# fpga.net
KiCad netlist of a schematic drawn in EAGLE
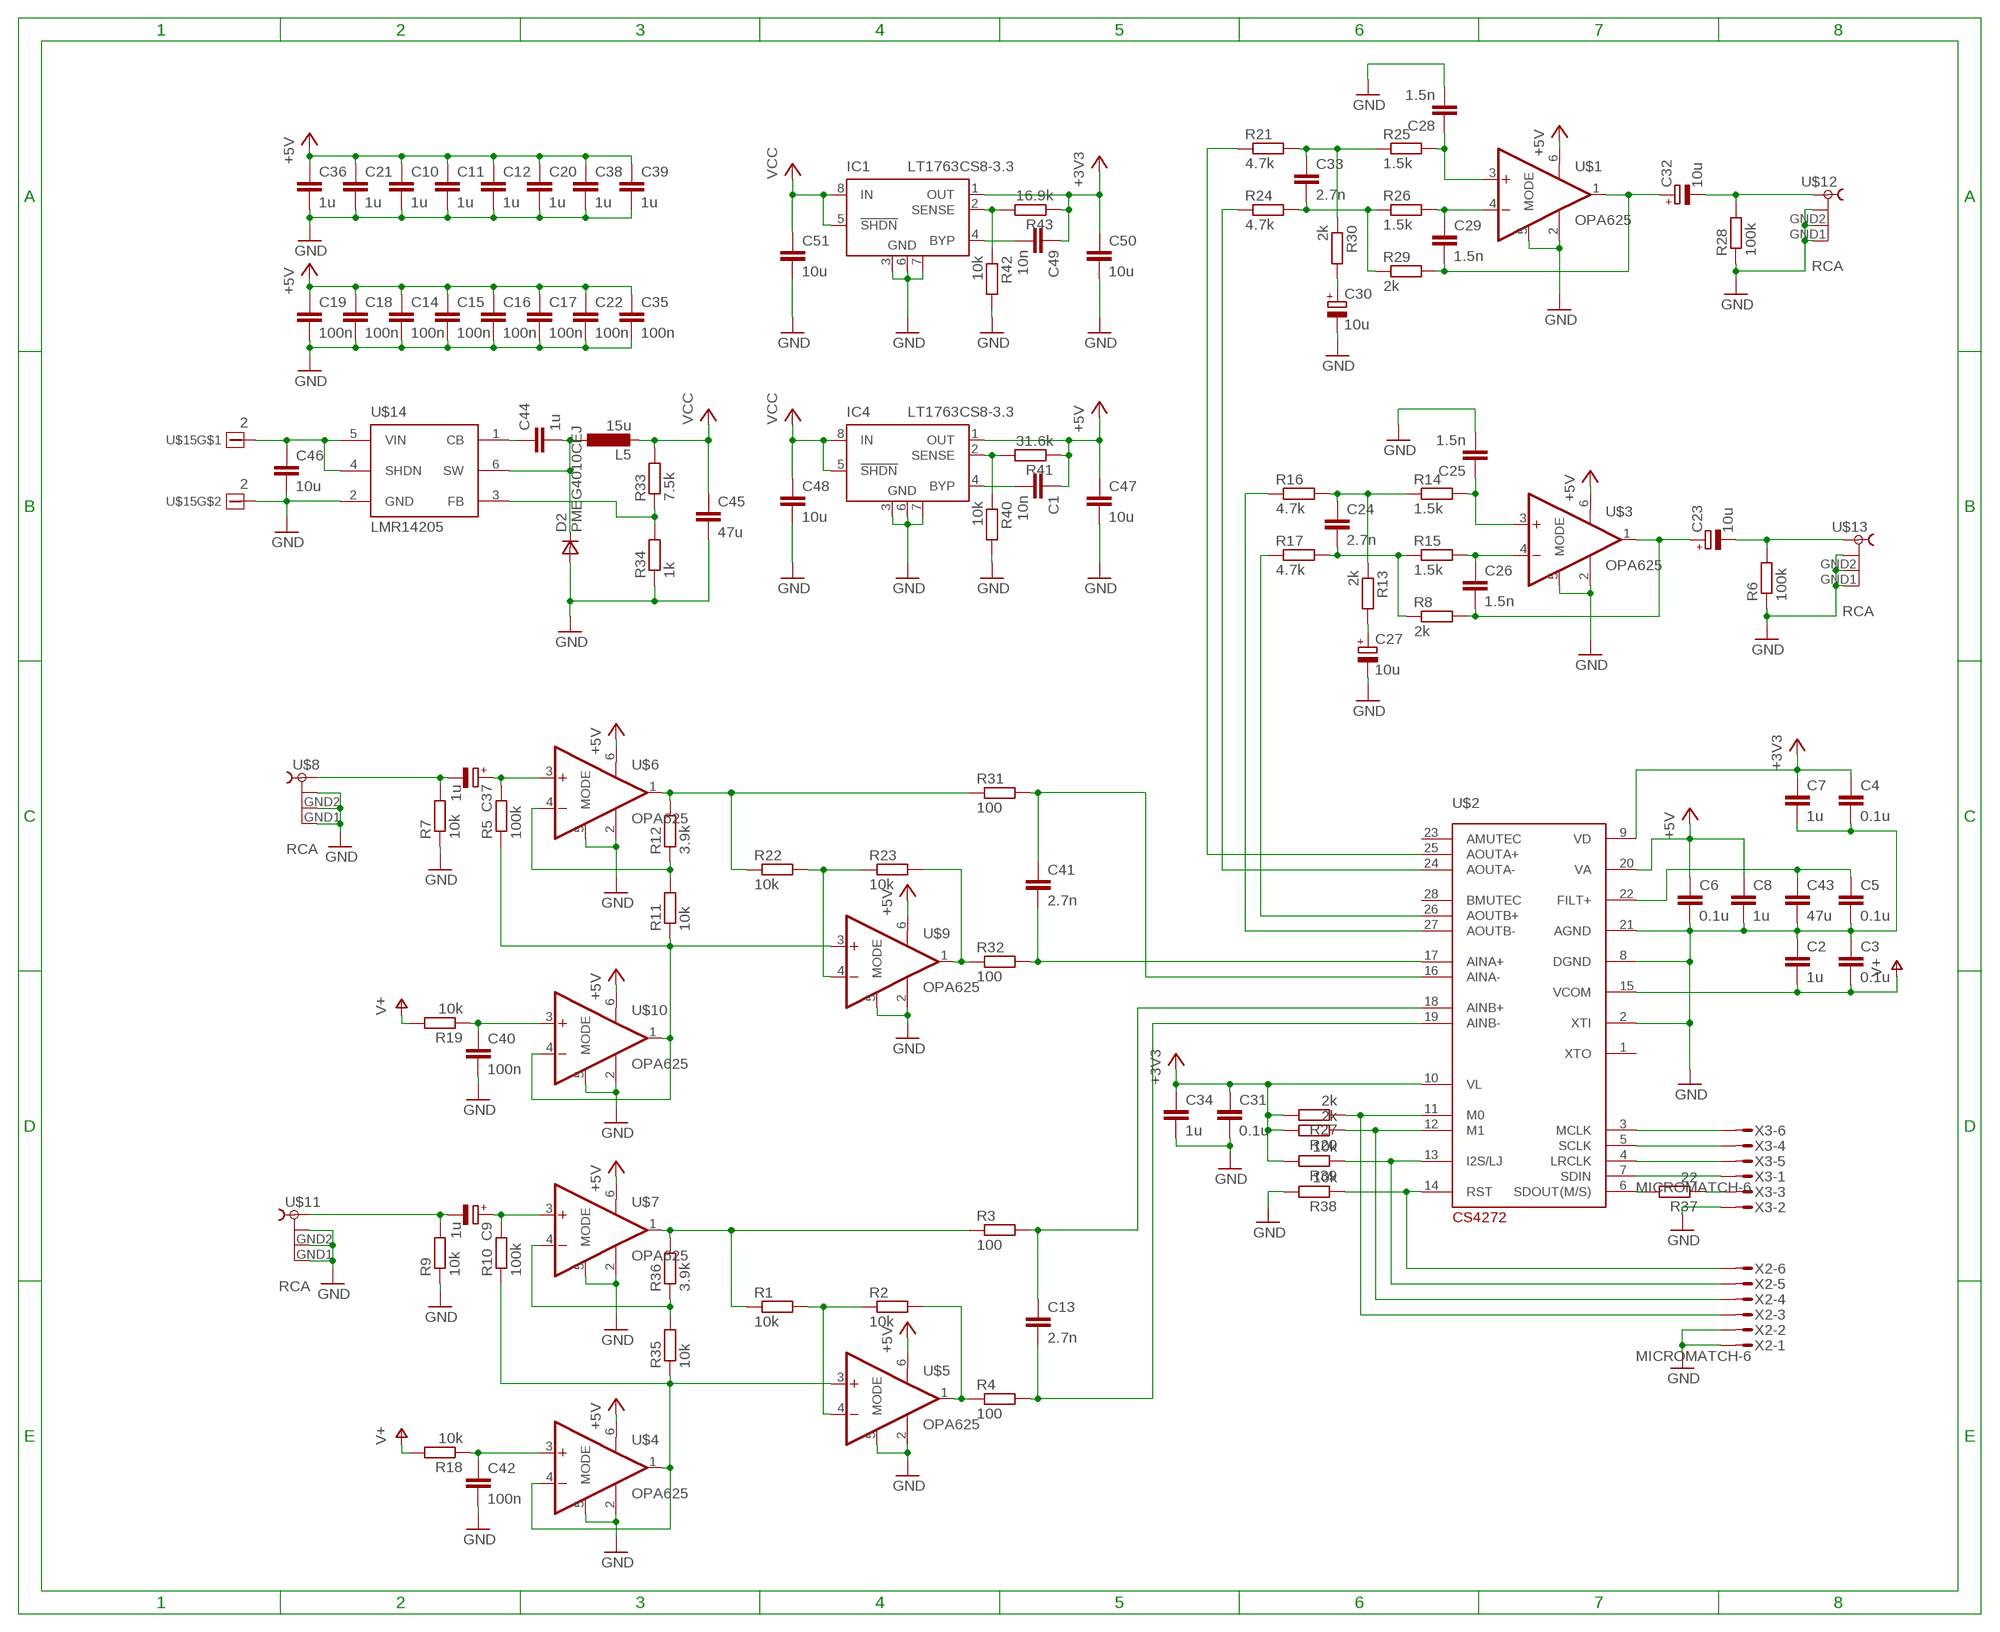
[diagram p0: schematic, sheet 1]

(export (version "E")
  (design (tool "Eeschema 10.0.6"))
  (components
    (comp (ref "C1")
      (value "10n")
      (footprint "eagle-import:C0603K")
      (libsource (lib "eagle-import") (part "C-EUC0603K"))
    )
    (comp (ref "C2")
      (value "1u")
      (footprint "eagle-import:C0603K")
      (libsource (lib "eagle-import") (part "C-EUC0603K"))
    )
    (comp (ref "C3")
      (value "0.1u")
      (footprint "eagle-import:C0603K")
      (libsource (lib "eagle-import") (part "C-EUC0603K"))
    )
    (comp (ref "C4")
      (value "0.1u")
      (footprint "eagle-import:C0603K")
      (libsource (lib "eagle-import") (part "C-EUC0603K"))
    )
    (comp (ref "C5")
      (value "0.1u")
      (footprint "eagle-import:C0603K")
      (libsource (lib "eagle-import") (part "C-EUC0603K"))
    )
    (comp (ref "C6")
      (value "0.1u")
      (footprint "eagle-import:C0603K")
      (libsource (lib "eagle-import") (part "C-EUC0603K"))
    )
    (comp (ref "C7")
      (value "1u")
      (footprint "eagle-import:C0603K")
      (libsource (lib "eagle-import") (part "C-EUC0603K"))
    )
    (comp (ref "C8")
      (value "1u")
      (footprint "eagle-import:C0603K")
      (libsource (lib "eagle-import") (part "C-EUC0603K"))
    )
    (comp (ref "C9")
      (value "1u")
      (footprint "eagle-import:153CLV-0405")
      (libsource (lib "eagle-import") (part "CPOL-EU153CLV-0405"))
    )
    (comp (ref "C10")
      (value "1u")
      (footprint "eagle-import:C0603K")
      (libsource (lib "eagle-import") (part "C-EUC0603K"))
    )
    (comp (ref "C11")
      (value "1u")
      (footprint "eagle-import:C0603K")
      (libsource (lib "eagle-import") (part "C-EUC0603K"))
    )
    (comp (ref "C12")
      (value "1u")
      (footprint "eagle-import:C0603K")
      (libsource (lib "eagle-import") (part "C-EUC0603K"))
    )
    (comp (ref "C13")
      (value "2.7n")
      (footprint "eagle-import:C0603K")
      (libsource (lib "eagle-import") (part "C-EUC0603K"))
    )
    (comp (ref "C14")
      (value "100n")
      (footprint "eagle-import:C0603K")
      (libsource (lib "eagle-import") (part "C-EUC0603K"))
    )
    (comp (ref "C15")
      (value "100n")
      (footprint "eagle-import:C0603K")
      (libsource (lib "eagle-import") (part "C-EUC0603K"))
    )
    (comp (ref "C16")
      (value "100n")
      (footprint "eagle-import:C0603K")
      (libsource (lib "eagle-import") (part "C-EUC0603K"))
    )
    (comp (ref "C17")
      (value "100n")
      (footprint "eagle-import:C0603K")
      (libsource (lib "eagle-import") (part "C-EUC0603K"))
    )
    (comp (ref "C18")
      (value "100n")
      (footprint "eagle-import:C0603K")
      (libsource (lib "eagle-import") (part "C-EUC0603K"))
    )
    (comp (ref "C19")
      (value "100n")
      (footprint "eagle-import:C0603K")
      (libsource (lib "eagle-import") (part "C-EUC0603K"))
    )
    (comp (ref "C20")
      (value "1u")
      (footprint "eagle-import:C0603K")
      (libsource (lib "eagle-import") (part "C-EUC0603K"))
    )
    (comp (ref "C21")
      (value "1u")
      (footprint "eagle-import:C0603K")
      (libsource (lib "eagle-import") (part "C-EUC0603K"))
    )
    (comp (ref "C22")
      (value "100n")
      (footprint "eagle-import:C0603K")
      (libsource (lib "eagle-import") (part "C-EUC0603K"))
    )
    (comp (ref "C23")
      (value "10u")
      (footprint "eagle-import:153CLV-0405")
      (libsource (lib "eagle-import") (part "CPOL-EU153CLV-0405"))
    )
    (comp (ref "C24")
      (value "2.7n")
      (footprint "eagle-import:C0603K")
      (libsource (lib "eagle-import") (part "C-EUC0603K"))
    )
    (comp (ref "C25")
      (value "1.5n")
      (footprint "eagle-import:C0603K")
      (libsource (lib "eagle-import") (part "C-EUC0603K"))
    )
    (comp (ref "C26")
      (value "1.5n")
      (footprint "eagle-import:C0603K")
      (libsource (lib "eagle-import") (part "C-EUC0603K"))
    )
    (comp (ref "C27")
      (value "10u")
      (footprint "eagle-import:153CLV-0405")
      (libsource (lib "eagle-import") (part "CPOL-EU153CLV-0405"))
    )
    (comp (ref "C28")
      (value "1.5n")
      (footprint "eagle-import:C0603K")
      (libsource (lib "eagle-import") (part "C-EUC0603K"))
    )
    (comp (ref "C29")
      (value "1.5n")
      (footprint "eagle-import:C0603K")
      (libsource (lib "eagle-import") (part "C-EUC0603K"))
    )
    (comp (ref "C30")
      (value "10u")
      (footprint "eagle-import:153CLV-0405")
      (libsource (lib "eagle-import") (part "CPOL-EU153CLV-0405"))
    )
    (comp (ref "C31")
      (value "0.1u")
      (footprint "eagle-import:C0603K")
      (libsource (lib "eagle-import") (part "C-EUC0603K"))
    )
    (comp (ref "C32")
      (value "10u")
      (footprint "eagle-import:153CLV-0405")
      (libsource (lib "eagle-import") (part "CPOL-EU153CLV-0405"))
    )
    (comp (ref "C33")
      (value "2.7n")
      (footprint "eagle-import:C0603K")
      (libsource (lib "eagle-import") (part "C-EUC0603K"))
    )
    (comp (ref "C34")
      (value "1u")
      (footprint "eagle-import:C0603K")
      (libsource (lib "eagle-import") (part "C-EUC0603K"))
    )
    (comp (ref "C35")
      (value "100n")
      (footprint "eagle-import:C0603K")
      (libsource (lib "eagle-import") (part "C-EUC0603K"))
    )
    (comp (ref "C36")
      (value "1u")
      (footprint "eagle-import:C0603K")
      (libsource (lib "eagle-import") (part "C-EUC0603K"))
    )
    (comp (ref "C37")
      (value "1u")
      (footprint "eagle-import:153CLV-0405")
      (libsource (lib "eagle-import") (part "CPOL-EU153CLV-0405"))
    )
    (comp (ref "C38")
      (value "1u")
      (footprint "eagle-import:C0603K")
      (libsource (lib "eagle-import") (part "C-EUC0603K"))
    )
    (comp (ref "C39")
      (value "1u")
      (footprint "eagle-import:C0603K")
      (libsource (lib "eagle-import") (part "C-EUC0603K"))
    )
    (comp (ref "C40")
      (value "100n")
      (footprint "eagle-import:C0603K")
      (libsource (lib "eagle-import") (part "C-EUC0603K"))
    )
    (comp (ref "C41")
      (value "2.7n")
      (footprint "eagle-import:C0603K")
      (libsource (lib "eagle-import") (part "C-EUC0603K"))
    )
    (comp (ref "C42")
      (value "100n")
      (footprint "eagle-import:C0603K")
      (libsource (lib "eagle-import") (part "C-EUC0603K"))
    )
    (comp (ref "C43")
      (value "47u")
      (footprint "eagle-import:C0805")
      (libsource (lib "eagle-import") (part "C-EUC0805"))
    )
    (comp (ref "C44")
      (value "1u")
      (footprint "eagle-import:C0603K")
      (libsource (lib "eagle-import") (part "C-EUC0603K"))
    )
    (comp (ref "C45")
      (value "47u")
      (footprint "eagle-import:C1206")
      (libsource (lib "eagle-import") (part "C-EUC1206"))
    )
    (comp (ref "C46")
      (value "10u")
      (footprint "eagle-import:C0805")
      (libsource (lib "eagle-import") (part "C-EUC0805"))
    )
    (comp (ref "C47")
      (value "10u")
      (footprint "eagle-import:C0603K")
      (libsource (lib "eagle-import") (part "C-EUC0603K"))
    )
    (comp (ref "C48")
      (value "10u")
      (footprint "eagle-import:C0603K")
      (libsource (lib "eagle-import") (part "C-EUC0603K"))
    )
    (comp (ref "C49")
      (value "10n")
      (footprint "eagle-import:C0603K")
      (libsource (lib "eagle-import") (part "C-EUC0603K"))
    )
    (comp (ref "C50")
      (value "10u")
      (footprint "eagle-import:C0603K")
      (libsource (lib "eagle-import") (part "C-EUC0603K"))
    )
    (comp (ref "C51")
      (value "10u")
      (footprint "eagle-import:C0603K")
      (libsource (lib "eagle-import") (part "C-EUC0603K"))
    )
    (comp (ref "D2")
      (value "PMEG4010CEJ")
      (footprint "eagle-import:SOD323")
      (fields (field (name "MPN") "CDSOD323-T05C"))
      (libsource (lib "eagle-import") (part "DSOD323"))
    )
    (comp (ref "IC1")
      (value "LT1763CS8-3.3")
      (footprint "eagle-import:SOIC8")
      (libsource (lib "eagle-import") (part "LT1763CS8-3.3"))
    )
    (comp (ref "IC4")
      (value "LT1763CS8-3.3")
      (footprint "eagle-import:SOIC8")
      (libsource (lib "eagle-import") (part "LT1763CS8-3.3"))
    )
    (comp (ref "L5")
      (value "15u")
      (footprint "eagle-import:AAA")
      (libsource (lib "eagle-import") (part "L-EU"))
    )
    (comp (ref "R1")
      (value "10k")
      (footprint "eagle-import:R0603")
      (libsource (lib "eagle-import") (part "R-EU_R0603"))
    )
    (comp (ref "R2")
      (value "10k")
      (footprint "eagle-import:R0603")
      (libsource (lib "eagle-import") (part "R-EU_R0603"))
    )
    (comp (ref "R3")
      (value "100")
      (footprint "eagle-import:R0603")
      (libsource (lib "eagle-import") (part "R-EU_R0603"))
    )
    (comp (ref "R4")
      (value "100")
      (footprint "eagle-import:R0603")
      (libsource (lib "eagle-import") (part "R-EU_R0603"))
    )
    (comp (ref "R5")
      (value "100k")
      (footprint "eagle-import:R0603")
      (libsource (lib "eagle-import") (part "R-EU_R0603"))
    )
    (comp (ref "R6")
      (value "100k")
      (footprint "eagle-import:R0603")
      (libsource (lib "eagle-import") (part "R-EU_R0603"))
    )
    (comp (ref "R7")
      (value "10k")
      (footprint "eagle-import:R0603")
      (libsource (lib "eagle-import") (part "R-EU_R0603"))
    )
    (comp (ref "R8")
      (value "2k")
      (footprint "eagle-import:R0603")
      (libsource (lib "eagle-import") (part "R-EU_R0603"))
    )
    (comp (ref "R9")
      (value "10k")
      (footprint "eagle-import:R0603")
      (libsource (lib "eagle-import") (part "R-EU_R0603"))
    )
    (comp (ref "R10")
      (value "100k")
      (footprint "eagle-import:R0603")
      (libsource (lib "eagle-import") (part "R-EU_R0603"))
    )
    (comp (ref "R11")
      (value "10k")
      (footprint "eagle-import:R0603")
      (libsource (lib "eagle-import") (part "R-EU_R0603"))
    )
    (comp (ref "R12")
      (value "3.9k")
      (footprint "eagle-import:R0603")
      (libsource (lib "eagle-import") (part "R-EU_R0603"))
    )
    (comp (ref "R13")
      (value "2k")
      (footprint "eagle-import:R0603")
      (libsource (lib "eagle-import") (part "R-EU_R0603"))
    )
    (comp (ref "R14")
      (value "1.5k")
      (footprint "eagle-import:R0603")
      (libsource (lib "eagle-import") (part "R-EU_R0603"))
    )
    (comp (ref "R15")
      (value "1.5k")
      (footprint "eagle-import:R0603")
      (libsource (lib "eagle-import") (part "R-EU_R0603"))
    )
    (comp (ref "R16")
      (value "4.7k")
      (footprint "eagle-import:R0603")
      (libsource (lib "eagle-import") (part "R-EU_R0603"))
    )
    (comp (ref "R17")
      (value "4.7k")
      (footprint "eagle-import:R0603")
      (libsource (lib "eagle-import") (part "R-EU_R0603"))
    )
    (comp (ref "R18")
      (value "10k")
      (footprint "eagle-import:R0603")
      (libsource (lib "eagle-import") (part "R-EU_R0603"))
    )
    (comp (ref "R19")
      (value "10k")
      (footprint "eagle-import:R0603")
      (libsource (lib "eagle-import") (part "R-EU_R0603"))
    )
    (comp (ref "R20")
      (value "2k")
      (footprint "eagle-import:R0603")
      (libsource (lib "eagle-import") (part "R-EU_R0603"))
    )
    (comp (ref "R21")
      (value "4.7k")
      (footprint "eagle-import:R0603")
      (libsource (lib "eagle-import") (part "R-EU_R0603"))
    )
    (comp (ref "R22")
      (value "10k")
      (footprint "eagle-import:R0603")
      (libsource (lib "eagle-import") (part "R-EU_R0603"))
    )
    (comp (ref "R23")
      (value "10k")
      (footprint "eagle-import:R0603")
      (libsource (lib "eagle-import") (part "R-EU_R0603"))
    )
    (comp (ref "R24")
      (value "4.7k")
      (footprint "eagle-import:R0603")
      (libsource (lib "eagle-import") (part "R-EU_R0603"))
    )
    (comp (ref "R25")
      (value "1.5k")
      (footprint "eagle-import:R0603")
      (libsource (lib "eagle-import") (part "R-EU_R0603"))
    )
    (comp (ref "R26")
      (value "1.5k")
      (footprint "eagle-import:R0603")
      (libsource (lib "eagle-import") (part "R-EU_R0603"))
    )
    (comp (ref "R27")
      (value "2k")
      (footprint "eagle-import:R0603")
      (libsource (lib "eagle-import") (part "R-EU_R0603"))
    )
    (comp (ref "R28")
      (value "100k")
      (footprint "eagle-import:R0603")
      (libsource (lib "eagle-import") (part "R-EU_R0603"))
    )
    (comp (ref "R29")
      (value "2k")
      (footprint "eagle-import:R0603")
      (libsource (lib "eagle-import") (part "R-EU_R0603"))
    )
    (comp (ref "R30")
      (value "2k")
      (footprint "eagle-import:R0603")
      (libsource (lib "eagle-import") (part "R-EU_R0603"))
    )
    (comp (ref "R31")
      (value "100")
      (footprint "eagle-import:R0603")
      (libsource (lib "eagle-import") (part "R-EU_R0603"))
    )
    (comp (ref "R32")
      (value "100")
      (footprint "eagle-import:R0603")
      (libsource (lib "eagle-import") (part "R-EU_R0603"))
    )
    (comp (ref "R33")
      (value "7.5k")
      (footprint "eagle-import:R0603")
      (libsource (lib "eagle-import") (part "R-EU_R0603"))
    )
    (comp (ref "R34")
      (value "1k")
      (footprint "eagle-import:R0603")
      (libsource (lib "eagle-import") (part "R-EU_R0603"))
    )
    (comp (ref "R35")
      (value "10k")
      (footprint "eagle-import:R0603")
      (libsource (lib "eagle-import") (part "R-EU_R0603"))
    )
    (comp (ref "R36")
      (value "3.9k")
      (footprint "eagle-import:R0603")
      (libsource (lib "eagle-import") (part "R-EU_R0603"))
    )
    (comp (ref "R37")
      (value "22")
      (footprint "eagle-import:R0603")
      (libsource (lib "eagle-import") (part "R-EU_R0603"))
    )
    (comp (ref "R38")
      (value "10k")
      (footprint "eagle-import:R0603")
      (libsource (lib "eagle-import") (part "R-EU_R0603"))
    )
    (comp (ref "R39")
      (value "10k")
      (footprint "eagle-import:R0603")
      (libsource (lib "eagle-import") (part "R-EU_R0603"))
    )
    (comp (ref "R40")
      (value "10k")
      (footprint "eagle-import:R0603")
      (libsource (lib "eagle-import") (part "R-EU_R0603"))
    )
    (comp (ref "R41")
      (value "31.6k")
      (footprint "eagle-import:R0603")
      (libsource (lib "eagle-import") (part "R-EU_R0603"))
    )
    (comp (ref "R42")
      (value "10k")
      (footprint "eagle-import:R0603")
      (libsource (lib "eagle-import") (part "R-EU_R0603"))
    )
    (comp (ref "R43")
      (value "16.9k")
      (footprint "eagle-import:R0603")
      (libsource (lib "eagle-import") (part "R-EU_R0603"))
    )
    (comp (ref "U$1")
      (value "OPA625")
      (footprint "eagle-import:SOT23-6")
      (libsource (lib "eagle-import") (part "OPA625"))
    )
    (comp (ref "U$2")
      (value "CS4272")
      (footprint "eagle-import:TSSOP28")
      (libsource (lib "eagle-import") (part "CS4272"))
    )
    (comp (ref "U$3")
      (value "OPA625")
      (footprint "eagle-import:SOT23-6")
      (libsource (lib "eagle-import") (part "OPA625"))
    )
    (comp (ref "U$4")
      (value "OPA625")
      (footprint "eagle-import:SOT23-6")
      (libsource (lib "eagle-import") (part "OPA625"))
    )
    (comp (ref "U$5")
      (value "OPA625")
      (footprint "eagle-import:SOT23-6")
      (libsource (lib "eagle-import") (part "OPA625"))
    )
    (comp (ref "U$6")
      (value "OPA625")
      (footprint "eagle-import:SOT23-6")
      (libsource (lib "eagle-import") (part "OPA625"))
    )
    (comp (ref "U$7")
      (value "OPA625")
      (footprint "eagle-import:SOT23-6")
      (libsource (lib "eagle-import") (part "OPA625"))
    )
    (comp (ref "U$8")
      (value "RCA")
      (footprint "eagle-import:RCA")
      (libsource (lib "eagle-import") (part "RCA"))
    )
    (comp (ref "U$9")
      (value "OPA625")
      (footprint "eagle-import:SOT23-6")
      (libsource (lib "eagle-import") (part "OPA625"))
    )
    (comp (ref "U$10")
      (value "OPA625")
      (footprint "eagle-import:SOT23-6")
      (libsource (lib "eagle-import") (part "OPA625"))
    )
    (comp (ref "U$11")
      (value "RCA")
      (footprint "eagle-import:RCA")
      (libsource (lib "eagle-import") (part "RCA"))
    )
    (comp (ref "U$12")
      (value "RCA")
      (footprint "eagle-import:RCA")
      (libsource (lib "eagle-import") (part "RCA"))
    )
    (comp (ref "U$13")
      (value "RCA")
      (footprint "eagle-import:RCA")
      (libsource (lib "eagle-import") (part "RCA"))
    )
    (comp (ref "U$14")
      (value "LMR14205")
      (footprint "eagle-import:TSOT23-6_DDC")
      (libsource (lib "eagle-import") (part "LMR14205"))
    )
    (comp (ref "U$15") (value "2") (footprint "eagle-import:2") (libsource (lib "eagle-import") (part "2")))
    (comp (ref "X2")
      (value "MICROMATCH-6")
      (footprint "eagle-import:MICROMATCH-6")
      (fields (field (name "MPN") "7-215464-6"))
      (libsource (lib "eagle-import") (part "MICROMATCH-6"))
    )
    (comp (ref "X3")
      (value "MICROMATCH-6")
      (footprint "eagle-import:MICROMATCH-6")
      (fields (field (name "MPN") "7-215464-6"))
      (libsource (lib "eagle-import") (part "MICROMATCH-6"))
    )
  )
  (nets
    (net (code "1") (name "+3V3") (class "Default")
      (node (ref "C31") (pin "1") (pinfunction "1_1") (pintype "passive"))
      (node (ref "C34") (pin "1") (pinfunction "1_1") (pintype "passive"))
      (node (ref "C4") (pin "1") (pinfunction "1_1") (pintype "passive"))
      (node (ref "C49") (pin "1") (pinfunction "1_1") (pintype "passive"))
      (node (ref "C50") (pin "1") (pinfunction "1_1") (pintype "passive"))
      (node (ref "C7") (pin "1") (pinfunction "1_1") (pintype "passive"))
      (node (ref "IC1") (pin "1") (pinfunction "OUT_1") (pintype "passive"))
      (node (ref "R20") (pin "2") (pinfunction "2_2") (pintype "passive"))
      (node (ref "R27") (pin "2") (pinfunction "2_2") (pintype "passive"))
      (node (ref "R39") (pin "2") (pinfunction "2_2") (pintype "passive"))
      (node (ref "R43") (pin "1") (pinfunction "1_1") (pintype "passive"))
      (node (ref "U$2") (pin "10") (pinfunction "VL_10") (pintype "bidirectional"))
      (node (ref "U$2") (pin "9") (pinfunction "VD_9") (pintype "bidirectional"))
    )
    (net (code "2") (name "+5V") (class "Default")
      (node (ref "C1") (pin "1") (pinfunction "1_1") (pintype "passive"))
      (node (ref "C10") (pin "1") (pinfunction "1_1") (pintype "passive"))
      (node (ref "C11") (pin "1") (pinfunction "1_1") (pintype "passive"))
      (node (ref "C12") (pin "1") (pinfunction "1_1") (pintype "passive"))
      (node (ref "C14") (pin "1") (pinfunction "1_1") (pintype "passive"))
      (node (ref "C15") (pin "1") (pinfunction "1_1") (pintype "passive"))
      (node (ref "C16") (pin "1") (pinfunction "1_1") (pintype "passive"))
      (node (ref "C17") (pin "1") (pinfunction "1_1") (pintype "passive"))
      (node (ref "C18") (pin "1") (pinfunction "1_1") (pintype "passive"))
      (node (ref "C19") (pin "1") (pinfunction "1_1") (pintype "passive"))
      (node (ref "C20") (pin "1") (pinfunction "1_1") (pintype "passive"))
      (node (ref "C21") (pin "1") (pinfunction "1_1") (pintype "passive"))
      (node (ref "C22") (pin "1") (pinfunction "1_1") (pintype "passive"))
      (node (ref "C35") (pin "1") (pinfunction "1_1") (pintype "passive"))
      (node (ref "C36") (pin "1") (pinfunction "1_1") (pintype "passive"))
      (node (ref "C38") (pin "1") (pinfunction "1_1") (pintype "passive"))
      (node (ref "C39") (pin "1") (pinfunction "1_1") (pintype "passive"))
      (node (ref "C47") (pin "1") (pinfunction "1_1") (pintype "passive"))
      (node (ref "C6") (pin "1") (pinfunction "1_1") (pintype "passive"))
      (node (ref "C8") (pin "1") (pinfunction "1_1") (pintype "passive"))
      (node (ref "IC4") (pin "1") (pinfunction "OUT_1") (pintype "passive"))
      (node (ref "R41") (pin "1") (pinfunction "1_1") (pintype "passive"))
      (node (ref "U$1") (pin "6") (pinfunction "V+_6") (pintype "power_in"))
      (node (ref "U$10") (pin "6") (pinfunction "V+_6") (pintype "power_in"))
      (node (ref "U$2") (pin "20") (pinfunction "VA_20") (pintype "bidirectional"))
      (node (ref "U$3") (pin "6") (pinfunction "V+_6") (pintype "power_in"))
      (node (ref "U$4") (pin "6") (pinfunction "V+_6") (pintype "power_in"))
      (node (ref "U$5") (pin "6") (pinfunction "V+_6") (pintype "power_in"))
      (node (ref "U$6") (pin "6") (pinfunction "V+_6") (pintype "power_in"))
      (node (ref "U$7") (pin "6") (pinfunction "V+_6") (pintype "power_in"))
      (node (ref "U$9") (pin "6") (pinfunction "V+_6") (pintype "power_in"))
    )
    (net (code "3") (name "GND") (class "Default")
      (node (ref "C10") (pin "2") (pinfunction "2_2") (pintype "passive"))
      (node (ref "C11") (pin "2") (pinfunction "2_2") (pintype "passive"))
      (node (ref "C12") (pin "2") (pinfunction "2_2") (pintype "passive"))
      (node (ref "C14") (pin "2") (pinfunction "2_2") (pintype "passive"))
      (node (ref "C15") (pin "2") (pinfunction "2_2") (pintype "passive"))
      (node (ref "C16") (pin "2") (pinfunction "2_2") (pintype "passive"))
      (node (ref "C17") (pin "2") (pinfunction "2_2") (pintype "passive"))
      (node (ref "C18") (pin "2") (pinfunction "2_2") (pintype "passive"))
      (node (ref "C19") (pin "2") (pinfunction "2_2") (pintype "passive"))
      (node (ref "C2") (pin "1") (pinfunction "1_1") (pintype "passive"))
      (node (ref "C20") (pin "2") (pinfunction "2_2") (pintype "passive"))
      (node (ref "C21") (pin "2") (pinfunction "2_2") (pintype "passive"))
      (node (ref "C22") (pin "2") (pinfunction "2_2") (pintype "passive"))
      (node (ref "C25") (pin "2") (pinfunction "2_2") (pintype "passive"))
      (node (ref "C27") (pin "-") (pinfunction "-_-") (pintype "passive"))
      (node (ref "C28") (pin "2") (pinfunction "2_2") (pintype "passive"))
      (node (ref "C3") (pin "1") (pinfunction "1_1") (pintype "passive"))
      (node (ref "C30") (pin "-") (pinfunction "-_-") (pintype "passive"))
      (node (ref "C31") (pin "2") (pinfunction "2_2") (pintype "passive"))
      (node (ref "C34") (pin "2") (pinfunction "2_2") (pintype "passive"))
      (node (ref "C35") (pin "2") (pinfunction "2_2") (pintype "passive"))
      (node (ref "C36") (pin "2") (pinfunction "2_2") (pintype "passive"))
      (node (ref "C38") (pin "2") (pinfunction "2_2") (pintype "passive"))
      (node (ref "C39") (pin "2") (pinfunction "2_2") (pintype "passive"))
      (node (ref "C4") (pin "2") (pinfunction "2_2") (pintype "passive"))
      (node (ref "C40") (pin "2") (pinfunction "2_2") (pintype "passive"))
      (node (ref "C42") (pin "2") (pinfunction "2_2") (pintype "passive"))
      (node (ref "C43") (pin "2") (pinfunction "2_2") (pintype "passive"))
      (node (ref "C45") (pin "2") (pinfunction "2_2") (pintype "passive"))
      (node (ref "C46") (pin "2") (pinfunction "2_2") (pintype "passive"))
      (node (ref "C47") (pin "2") (pinfunction "2_2") (pintype "passive"))
      (node (ref "C48") (pin "2") (pinfunction "2_2") (pintype "passive"))
      (node (ref "C5") (pin "2") (pinfunction "2_2") (pintype "passive"))
      (node (ref "C50") (pin "2") (pinfunction "2_2") (pintype "passive"))
      (node (ref "C51") (pin "2") (pinfunction "2_2") (pintype "passive"))
      (node (ref "C6") (pin "2") (pinfunction "2_2") (pintype "passive"))
      (node (ref "C7") (pin "2") (pinfunction "2_2") (pintype "passive"))
      (node (ref "C8") (pin "2") (pinfunction "2_2") (pintype "passive"))
      (node (ref "D2") (pin "2") (pinfunction "A_2") (pintype "passive"))
      (node (ref "IC1") (pin "3") (pinfunction "GND_3") (pintype "power_in"))
      (node (ref "IC1") (pin "6") (pinfunction "GND_6") (pintype "power_in"))
      (node (ref "IC1") (pin "7") (pinfunction "GND_7") (pintype "power_in"))
      (node (ref "IC4") (pin "3") (pinfunction "GND_3") (pintype "power_in"))
      (node (ref "IC4") (pin "6") (pinfunction "GND_6") (pintype "power_in"))
      (node (ref "IC4") (pin "7") (pinfunction "GND_7") (pintype "power_in"))
      (node (ref "R28") (pin "1") (pinfunction "1_1") (pintype "passive"))
      (node (ref "R34") (pin "1") (pinfunction "1_1") (pintype "passive"))
      (node (ref "R38") (pin "2") (pinfunction "2_2") (pintype "passive"))
      (node (ref "R40") (pin "2") (pinfunction "2_2") (pintype "passive"))
      (node (ref "R42") (pin "2") (pinfunction "2_2") (pintype "passive"))
      (node (ref "R6") (pin "1") (pinfunction "1_1") (pintype "passive"))
      (node (ref "R7") (pin "1") (pinfunction "1_1") (pintype "passive"))
      (node (ref "R9") (pin "1") (pinfunction "1_1") (pintype "passive"))
      (node (ref "U$1") (pin "2") (pinfunction "V-_2") (pintype "power_in"))
      (node (ref "U$1") (pin "5") (pinfunction "MODE_5") (pintype "bidirectional"))
      (node (ref "U$10") (pin "2") (pinfunction "V-_2") (pintype "power_in"))
      (node (ref "U$10") (pin "5") (pinfunction "MODE_5") (pintype "bidirectional"))
      (node (ref "U$11") (pin "GND1") (pinfunction "4_GND1") (pintype "passive"))
      (node (ref "U$11") (pin "GND2") (pinfunction "3_GND2") (pintype "passive"))
      (node (ref "U$11") (pin "GND3") (pinfunction "2_GND3") (pintype "passive"))
      (node (ref "U$12") (pin "GND1") (pinfunction "4_GND1") (pintype "passive"))
      (node (ref "U$12") (pin "GND2") (pinfunction "3_GND2") (pintype "passive"))
      (node (ref "U$12") (pin "GND3") (pinfunction "2_GND3") (pintype "passive"))
      (node (ref "U$13") (pin "GND1") (pinfunction "4_GND1") (pintype "passive"))
      (node (ref "U$13") (pin "GND2") (pinfunction "3_GND2") (pintype "passive"))
      (node (ref "U$13") (pin "GND3") (pinfunction "2_GND3") (pintype "passive"))
      (node (ref "U$14") (pin "2") (pinfunction "GND_2") (pintype "input"))
      (node (ref "U$15") (pin "P$2") (pinfunction "1_P$2") (pintype "passive"))
      (node (ref "U$2") (pin "2") (pinfunction "XTI_2") (pintype "bidirectional"))
      (node (ref "U$2") (pin "21") (pinfunction "AGND_21") (pintype "bidirectional"))
      (node (ref "U$2") (pin "8") (pinfunction "DGND_8") (pintype "bidirectional"))
      (node (ref "U$3") (pin "2") (pinfunction "V-_2") (pintype "power_in"))
      (node (ref "U$3") (pin "5") (pinfunction "MODE_5") (pintype "bidirectional"))
      (node (ref "U$4") (pin "2") (pinfunction "V-_2") (pintype "power_in"))
      (node (ref "U$4") (pin "5") (pinfunction "MODE_5") (pintype "bidirectional"))
      (node (ref "U$5") (pin "2") (pinfunction "V-_2") (pintype "power_in"))
      (node (ref "U$5") (pin "5") (pinfunction "MODE_5") (pintype "bidirectional"))
      (node (ref "U$6") (pin "2") (pinfunction "V-_2") (pintype "power_in"))
      (node (ref "U$6") (pin "5") (pinfunction "MODE_5") (pintype "bidirectional"))
      (node (ref "U$7") (pin "2") (pinfunction "V-_2") (pintype "power_in"))
      (node (ref "U$7") (pin "5") (pinfunction "MODE_5") (pintype "bidirectional"))
      (node (ref "U$8") (pin "GND1") (pinfunction "4_GND1") (pintype "passive"))
      (node (ref "U$8") (pin "GND2") (pinfunction "3_GND2") (pintype "passive"))
      (node (ref "U$8") (pin "GND3") (pinfunction "2_GND3") (pintype "passive"))
      (node (ref "U$9") (pin "2") (pinfunction "V-_2") (pintype "power_in"))
      (node (ref "U$9") (pin "5") (pinfunction "MODE_5") (pintype "bidirectional"))
      (node (ref "X2") (pin "1") (pinfunction "S_1") (pintype "passive"))
      (node (ref "X2") (pin "2") (pinfunction "S_2") (pintype "passive"))
      (node (ref "X3") (pin "2") (pinfunction "S_2") (pintype "passive"))
    )
    (net (code "4") (name "Net-(C24-Pad1)") (class "Default")
      (node (ref "C24") (pin "1") (pinfunction "1_1") (pintype "passive"))
      (node (ref "R13") (pin "1") (pinfunction "1_1") (pintype "passive"))
      (node (ref "R14") (pin "1") (pinfunction "1_1") (pintype "passive"))
      (node (ref "R16") (pin "2") (pinfunction "2_2") (pintype "passive"))
    )
    (net (code "5") (name "Net-(C24-Pad2)") (class "Default")
      (node (ref "C24") (pin "2") (pinfunction "2_2") (pintype "passive"))
      (node (ref "R15") (pin "1") (pinfunction "1_1") (pintype "passive"))
      (node (ref "R17") (pin "2") (pinfunction "2_2") (pintype "passive"))
      (node (ref "R8") (pin "1") (pinfunction "1_1") (pintype "passive"))
    )
    (net (code "6") (name "Net-(C27-Pad+)") (class "Default")
      (node (ref "C27") (pin "+") (pinfunction "+_+") (pintype "passive"))
      (node (ref "R13") (pin "2") (pinfunction "2_2") (pintype "passive"))
    )
    (net (code "7") (name "Net-(C30-Pad+)") (class "Default")
      (node (ref "C30") (pin "+") (pinfunction "+_+") (pintype "passive"))
      (node (ref "R30") (pin "2") (pinfunction "2_2") (pintype "passive"))
    )
    (net (code "8") (name "Net-(C33-Pad1)") (class "Default")
      (node (ref "C33") (pin "1") (pinfunction "1_1") (pintype "passive"))
      (node (ref "R21") (pin "2") (pinfunction "2_2") (pintype "passive"))
      (node (ref "R25") (pin "1") (pinfunction "1_1") (pintype "passive"))
      (node (ref "R30") (pin "1") (pinfunction "1_1") (pintype "passive"))
    )
    (net (code "9") (name "Net-(C33-Pad2)") (class "Default")
      (node (ref "C33") (pin "2") (pinfunction "2_2") (pintype "passive"))
      (node (ref "R24") (pin "2") (pinfunction "2_2") (pintype "passive"))
      (node (ref "R26") (pin "1") (pinfunction "1_1") (pintype "passive"))
      (node (ref "R29") (pin "1") (pinfunction "1_1") (pintype "passive"))
    )
    (net (code "10") (name "Net-(D2-C)") (class "Default")
      (node (ref "C44") (pin "2") (pinfunction "2_2") (pintype "passive"))
      (node (ref "D2") (pin "1") (pinfunction "C_1") (pintype "passive"))
      (node (ref "L5") (pin "P$1") (pinfunction "1_P$1") (pintype "passive"))
      (node (ref "U$14") (pin "6") (pinfunction "SW_6") (pintype "output"))
    )
    (net (code "11") (name "Net-(IC1-BYP)") (class "Default")
      (node (ref "C49") (pin "2") (pinfunction "2_2") (pintype "passive"))
      (node (ref "IC1") (pin "4") (pinfunction "BYP_4") (pintype "input"))
    )
    (net (code "12") (name "Net-(IC1-SENSE)") (class "Default")
      (node (ref "IC1") (pin "2") (pinfunction "SENSE_2") (pintype "input"))
      (node (ref "R42") (pin "1") (pinfunction "1_1") (pintype "passive"))
      (node (ref "R43") (pin "2") (pinfunction "2_2") (pintype "passive"))
    )
    (net (code "13") (name "Net-(IC4-BYP)") (class "Default")
      (node (ref "C1") (pin "2") (pinfunction "2_2") (pintype "passive"))
      (node (ref "IC4") (pin "4") (pinfunction "BYP_4") (pintype "input"))
    )
    (net (code "14") (name "Net-(IC4-SENSE)") (class "Default")
      (node (ref "IC4") (pin "2") (pinfunction "SENSE_2") (pintype "input"))
      (node (ref "R40") (pin "1") (pinfunction "1_1") (pintype "passive"))
      (node (ref "R41") (pin "2") (pinfunction "2_2") (pintype "passive"))
    )
    (net (code "15") (name "Net-(U$1-+IN)") (class "Default")
      (node (ref "C28") (pin "1") (pinfunction "1_1") (pintype "passive"))
      (node (ref "R25") (pin "2") (pinfunction "2_2") (pintype "passive"))
      (node (ref "U$1") (pin "3") (pinfunction "+IN_3") (pintype "input"))
    )
    (net (code "16") (name "Net-(U$1--IN)") (class "Default")
      (node (ref "C29") (pin "1") (pinfunction "1_1") (pintype "passive"))
      (node (ref "R26") (pin "2") (pinfunction "2_2") (pintype "passive"))
      (node (ref "U$1") (pin "4") (pinfunction "-IN_4") (pintype "input"))
    )
    (net (code "17") (name "Net-(U$1-OUT)") (class "Default")
      (node (ref "C29") (pin "2") (pinfunction "2_2") (pintype "passive"))
      (node (ref "C32") (pin "+") (pinfunction "+_+") (pintype "passive"))
      (node (ref "R29") (pin "2") (pinfunction "2_2") (pintype "passive"))
      (node (ref "U$1") (pin "1") (pinfunction "OUT_1") (pintype "output"))
    )
    (net (code "18") (name "Net-(U$2-AINA+)") (class "Default")
      (node (ref "C41") (pin "2") (pinfunction "2_2") (pintype "passive"))
      (node (ref "R32") (pin "2") (pinfunction "2_2") (pintype "passive"))
      (node (ref "U$2") (pin "17") (pinfunction "AINA+_17") (pintype "bidirectional"))
    )
    (net (code "19") (name "Net-(U$2-AINA-)") (class "Default")
      (node (ref "C41") (pin "1") (pinfunction "1_1") (pintype "passive"))
      (node (ref "R31") (pin "2") (pinfunction "2_2") (pintype "passive"))
      (node (ref "U$2") (pin "16") (pinfunction "AINA-_16") (pintype "bidirectional"))
    )
    (net (code "20") (name "Net-(U$2-AINB+)") (class "Default")
      (node (ref "C13") (pin "1") (pinfunction "1_1") (pintype "passive"))
      (node (ref "R3") (pin "2") (pinfunction "2_2") (pintype "passive"))
      (node (ref "U$2") (pin "18") (pinfunction "AINB+_18") (pintype "bidirectional"))
    )
    (net (code "21") (name "Net-(U$2-AINB-)") (class "Default")
      (node (ref "C13") (pin "2") (pinfunction "2_2") (pintype "passive"))
      (node (ref "R4") (pin "2") (pinfunction "2_2") (pintype "passive"))
      (node (ref "U$2") (pin "19") (pinfunction "AINB-_19") (pintype "bidirectional"))
    )
    (net (code "22") (name "Net-(U$2-AOUTA+)") (class "Default")
      (node (ref "R21") (pin "1") (pinfunction "1_1") (pintype "passive"))
      (node (ref "U$2") (pin "25") (pinfunction "AOUTA+_25") (pintype "bidirectional"))
    )
    (net (code "23") (name "Net-(U$2-AOUTA-)") (class "Default")
      (node (ref "R24") (pin "1") (pinfunction "1_1") (pintype "passive"))
      (node (ref "U$2") (pin "24") (pinfunction "AOUTA-_24") (pintype "bidirectional"))
    )
    (net (code "24") (name "Net-(U$2-AOUTB+)") (class "Default")
      (node (ref "R17") (pin "1") (pinfunction "1_1") (pintype "passive"))
      (node (ref "U$2") (pin "26") (pinfunction "AOUTB+_26") (pintype "bidirectional"))
    )
    (net (code "25") (name "Net-(U$2-AOUTB-)") (class "Default")
      (node (ref "R16") (pin "1") (pinfunction "1_1") (pintype "passive"))
      (node (ref "U$2") (pin "27") (pinfunction "AOUTB-_27") (pintype "bidirectional"))
    )
    (net (code "26") (name "Net-(U$2-FILT+)") (class "Default")
      (node (ref "C43") (pin "1") (pinfunction "1_1") (pintype "passive"))
      (node (ref "C5") (pin "1") (pinfunction "1_1") (pintype "passive"))
      (node (ref "U$2") (pin "22") (pinfunction "FILT+_22") (pintype "bidirectional"))
    )
    (net (code "27") (name "Net-(U$2-I2S{slash}LJ)") (class "Default")
      (node (ref "R39") (pin "1") (pinfunction "1_1") (pintype "passive"))
      (node (ref "U$2") (pin "13") (pinfunction "I2S/LJ_13") (pintype "bidirectional"))
      (node (ref "X2") (pin "5") (pinfunction "S_5") (pintype "passive"))
    )
    (net (code "28") (name "Net-(U$2-LRCLK)") (class "Default")
      (node (ref "U$2") (pin "4") (pinfunction "LRCLK_4") (pintype "bidirectional"))
      (node (ref "X3") (pin "5") (pinfunction "S_5") (pintype "passive"))
    )
    (net (code "29") (name "Net-(U$2-M0)") (class "Default")
      (node (ref "R27") (pin "1") (pinfunction "1_1") (pintype "passive"))
      (node (ref "U$2") (pin "11") (pinfunction "M0_11") (pintype "bidirectional"))
      (node (ref "X2") (pin "3") (pinfunction "S_3") (pintype "passive"))
    )
    (net (code "30") (name "Net-(U$2-M1)") (class "Default")
      (node (ref "R20") (pin "1") (pinfunction "1_1") (pintype "passive"))
      (node (ref "U$2") (pin "12") (pinfunction "M1_12") (pintype "bidirectional"))
      (node (ref "X2") (pin "4") (pinfunction "S_4") (pintype "passive"))
    )
    (net (code "31") (name "Net-(U$2-MCLK)") (class "Default")
      (node (ref "U$2") (pin "3") (pinfunction "MCLK_3") (pintype "bidirectional"))
      (node (ref "X3") (pin "6") (pinfunction "S_6") (pintype "passive"))
    )
    (net (code "32") (name "Net-(U$2-RST)") (class "Default")
      (node (ref "R38") (pin "1") (pinfunction "1_1") (pintype "passive"))
      (node (ref "U$2") (pin "14") (pinfunction "RST_14") (pintype "bidirectional"))
      (node (ref "X2") (pin "6") (pinfunction "S_6") (pintype "passive"))
    )
    (net (code "33") (name "Net-(U$2-SCLK)") (class "Default")
      (node (ref "U$2") (pin "5") (pinfunction "SCLK_5") (pintype "bidirectional"))
      (node (ref "X3") (pin "4") (pinfunction "S_4") (pintype "passive"))
    )
    (net (code "34") (name "Net-(U$2-SDIN)") (class "Default")
      (node (ref "U$2") (pin "7") (pinfunction "SDIN_7") (pintype "bidirectional"))
      (node (ref "X3") (pin "1") (pinfunction "S_1") (pintype "passive"))
    )
    (net (code "35") (name "Net-(U$2-SDOUT(M{slash}S))") (class "Default")
      (node (ref "R37") (pin "2") (pinfunction "2_2") (pintype "passive"))
      (node (ref "U$2") (pin "6") (pinfunction "SDOUT(M/S)_6") (pintype "bidirectional"))
    )
    (net (code "36") (name "Net-(U$3-+IN)") (class "Default")
      (node (ref "C25") (pin "1") (pinfunction "1_1") (pintype "passive"))
      (node (ref "R14") (pin "2") (pinfunction "2_2") (pintype "passive"))
      (node (ref "U$3") (pin "3") (pinfunction "+IN_3") (pintype "input"))
    )
    (net (code "37") (name "Net-(U$3--IN)") (class "Default")
      (node (ref "C26") (pin "1") (pinfunction "1_1") (pintype "passive"))
      (node (ref "R15") (pin "2") (pinfunction "2_2") (pintype "passive"))
      (node (ref "U$3") (pin "4") (pinfunction "-IN_4") (pintype "input"))
    )
    (net (code "38") (name "Net-(U$3-OUT)") (class "Default")
      (node (ref "C23") (pin "+") (pinfunction "+_+") (pintype "passive"))
      (node (ref "C26") (pin "2") (pinfunction "2_2") (pintype "passive"))
      (node (ref "R8") (pin "2") (pinfunction "2_2") (pintype "passive"))
      (node (ref "U$3") (pin "1") (pinfunction "OUT_1") (pintype "output"))
    )
    (net (code "39") (name "Net-(U$4-+IN)") (class "Default")
      (node (ref "C42") (pin "1") (pinfunction "1_1") (pintype "passive"))
      (node (ref "R18") (pin "1") (pinfunction "1_1") (pintype "passive"))
      (node (ref "U$4") (pin "3") (pinfunction "+IN_3") (pintype "input"))
    )
    (net (code "40") (name "Net-(U$4--IN)") (class "Default")
      (node (ref "R10") (pin "1") (pinfunction "1_1") (pintype "passive"))
      (node (ref "R35") (pin "1") (pinfunction "1_1") (pintype "passive"))
      (node (ref "U$4") (pin "1") (pinfunction "OUT_1") (pintype "output"))
      (node (ref "U$4") (pin "4") (pinfunction "-IN_4") (pintype "input"))
      (node (ref "U$5") (pin "3") (pinfunction "+IN_3") (pintype "input"))
    )
    (net (code "41") (name "Net-(U$5--IN)") (class "Default")
      (node (ref "R1") (pin "2") (pinfunction "2_2") (pintype "passive"))
      (node (ref "R2") (pin "1") (pinfunction "1_1") (pintype "passive"))
      (node (ref "U$5") (pin "4") (pinfunction "-IN_4") (pintype "input"))
    )
    (net (code "42") (name "Net-(U$5-OUT)") (class "Default")
      (node (ref "R2") (pin "2") (pinfunction "2_2") (pintype "passive"))
      (node (ref "R4") (pin "1") (pinfunction "1_1") (pintype "passive"))
      (node (ref "U$5") (pin "1") (pinfunction "OUT_1") (pintype "output"))
    )
    (net (code "43") (name "Net-(U$6-+IN)") (class "Default")
      (node (ref "C37") (pin "+") (pinfunction "+_+") (pintype "passive"))
      (node (ref "R5") (pin "2") (pinfunction "2_2") (pintype "passive"))
      (node (ref "U$6") (pin "3") (pinfunction "+IN_3") (pintype "input"))
    )
    (net (code "44") (name "Net-(U$6--IN)") (class "Default")
      (node (ref "R11") (pin "2") (pinfunction "2_2") (pintype "passive"))
      (node (ref "R12") (pin "1") (pinfunction "1_1") (pintype "passive"))
      (node (ref "U$6") (pin "4") (pinfunction "-IN_4") (pintype "input"))
    )
    (net (code "45") (name "Net-(U$6-OUT)") (class "Default")
      (node (ref "R12") (pin "2") (pinfunction "2_2") (pintype "passive"))
      (node (ref "R22") (pin "1") (pinfunction "1_1") (pintype "passive"))
      (node (ref "R31") (pin "1") (pinfunction "1_1") (pintype "passive"))
      (node (ref "U$6") (pin "1") (pinfunction "OUT_1") (pintype "output"))
    )
    (net (code "46") (name "Net-(U$7-+IN)") (class "Default")
      (node (ref "C9") (pin "+") (pinfunction "+_+") (pintype "passive"))
      (node (ref "R10") (pin "2") (pinfunction "2_2") (pintype "passive"))
      (node (ref "U$7") (pin "3") (pinfunction "+IN_3") (pintype "input"))
    )
    (net (code "47") (name "Net-(U$7--IN)") (class "Default")
      (node (ref "R35") (pin "2") (pinfunction "2_2") (pintype "passive"))
      (node (ref "R36") (pin "1") (pinfunction "1_1") (pintype "passive"))
      (node (ref "U$7") (pin "4") (pinfunction "-IN_4") (pintype "input"))
    )
    (net (code "48") (name "Net-(U$7-OUT)") (class "Default")
      (node (ref "R1") (pin "1") (pinfunction "1_1") (pintype "passive"))
      (node (ref "R3") (pin "1") (pinfunction "1_1") (pintype "passive"))
      (node (ref "R36") (pin "2") (pinfunction "2_2") (pintype "passive"))
      (node (ref "U$7") (pin "1") (pinfunction "OUT_1") (pintype "output"))
    )
    (net (code "49") (name "Net-(U$8-1)") (class "Default")
      (node (ref "C37") (pin "-") (pinfunction "-_-") (pintype "passive"))
      (node (ref "R7") (pin "2") (pinfunction "2_2") (pintype "passive"))
      (node (ref "U$8") (pin "S1") (pinfunction "1_S1") (pintype "passive"))
    )
    (net (code "50") (name "Net-(U$9--IN)") (class "Default")
      (node (ref "R22") (pin "2") (pinfunction "2_2") (pintype "passive"))
      (node (ref "R23") (pin "1") (pinfunction "1_1") (pintype "passive"))
      (node (ref "U$9") (pin "4") (pinfunction "-IN_4") (pintype "input"))
    )
    (net (code "51") (name "Net-(U$9-OUT)") (class "Default")
      (node (ref "R23") (pin "2") (pinfunction "2_2") (pintype "passive"))
      (node (ref "R32") (pin "1") (pinfunction "1_1") (pintype "passive"))
      (node (ref "U$9") (pin "1") (pinfunction "OUT_1") (pintype "output"))
    )
    (net (code "52") (name "Net-(U$10-+IN)") (class "Default")
      (node (ref "C40") (pin "1") (pinfunction "1_1") (pintype "passive"))
      (node (ref "R19") (pin "1") (pinfunction "1_1") (pintype "passive"))
      (node (ref "U$10") (pin "3") (pinfunction "+IN_3") (pintype "input"))
    )
    (net (code "53") (name "Net-(U$10--IN)") (class "Default")
      (node (ref "R11") (pin "1") (pinfunction "1_1") (pintype "passive"))
      (node (ref "R5") (pin "1") (pinfunction "1_1") (pintype "passive"))
      (node (ref "U$10") (pin "1") (pinfunction "OUT_1") (pintype "output"))
      (node (ref "U$10") (pin "4") (pinfunction "-IN_4") (pintype "input"))
      (node (ref "U$9") (pin "3") (pinfunction "+IN_3") (pintype "input"))
    )
    (net (code "54") (name "Net-(U$11-1)") (class "Default")
      (node (ref "C9") (pin "-") (pinfunction "-_-") (pintype "passive"))
      (node (ref "R9") (pin "2") (pinfunction "2_2") (pintype "passive"))
      (node (ref "U$11") (pin "S1") (pinfunction "1_S1") (pintype "passive"))
    )
    (net (code "55") (name "Net-(U$12-1)") (class "Default")
      (node (ref "C32") (pin "-") (pinfunction "-_-") (pintype "passive"))
      (node (ref "R28") (pin "2") (pinfunction "2_2") (pintype "passive"))
      (node (ref "U$12") (pin "S1") (pinfunction "1_S1") (pintype "passive"))
    )
    (net (code "56") (name "Net-(U$13-1)") (class "Default")
      (node (ref "C23") (pin "-") (pinfunction "-_-") (pintype "passive"))
      (node (ref "R6") (pin "2") (pinfunction "2_2") (pintype "passive"))
      (node (ref "U$13") (pin "S1") (pinfunction "1_S1") (pintype "passive"))
    )
    (net (code "57") (name "Net-(U$14-CB)") (class "Default")
      (node (ref "C44") (pin "1") (pinfunction "1_1") (pintype "passive"))
      (node (ref "U$14") (pin "1") (pinfunction "CB_1") (pintype "input"))
    )
    (net (code "58") (name "Net-(U$14-FB)") (class "Default")
      (node (ref "R33") (pin "1") (pinfunction "1_1") (pintype "passive"))
      (node (ref "R34") (pin "2") (pinfunction "2_2") (pintype "passive"))
      (node (ref "U$14") (pin "3") (pinfunction "FB_3") (pintype "input"))
    )
    (net (code "59") (name "Net-(U$14-SHDN)") (class "Default")
      (node (ref "C46") (pin "1") (pinfunction "1_1") (pintype "passive"))
      (node (ref "U$14") (pin "4") (pinfunction "SHDN_4") (pintype "bidirectional"))
      (node (ref "U$14") (pin "5") (pinfunction "VIN_5") (pintype "bidirectional"))
      (node (ref "U$15") (pin "P$1") (pinfunction "1_P$1") (pintype "passive"))
    )
    (net (code "60") (name "Net-(X3C-S)") (class "Default")
      (node (ref "R37") (pin "1") (pinfunction "1_1") (pintype "passive"))
      (node (ref "X3") (pin "3") (pinfunction "S_3") (pintype "passive"))
    )
    (net (code "61") (name "V+") (class "Default")
      (node (ref "C2") (pin "2") (pinfunction "2_2") (pintype "passive"))
      (node (ref "C3") (pin "2") (pinfunction "2_2") (pintype "passive"))
      (node (ref "R18") (pin "2") (pinfunction "2_2") (pintype "passive"))
      (node (ref "R19") (pin "2") (pinfunction "2_2") (pintype "passive"))
      (node (ref "U$2") (pin "15") (pinfunction "VCOM_15") (pintype "bidirectional"))
    )
    (net (code "62") (name "VCC") (class "Default")
      (node (ref "C45") (pin "1") (pinfunction "1_1") (pintype "passive"))
      (node (ref "C48") (pin "1") (pinfunction "1_1") (pintype "passive"))
      (node (ref "C51") (pin "1") (pinfunction "1_1") (pintype "passive"))
      (node (ref "IC1") (pin "5") (pinfunction "~{SHDN}_5") (pintype "input"))
      (node (ref "IC1") (pin "8") (pinfunction "IN_8") (pintype "input"))
      (node (ref "IC4") (pin "5") (pinfunction "~{SHDN}_5") (pintype "input"))
      (node (ref "IC4") (pin "8") (pinfunction "IN_8") (pintype "input"))
      (node (ref "L5") (pin "P$2") (pinfunction "2_P$2") (pintype "passive"))
      (node (ref "R33") (pin "2") (pinfunction "2_2") (pintype "passive"))
    )
    (net (code "63") (name "unconnected-(U$2-AMUTEC-Pad23)") (class "Default")
      (node (ref "U$2") (pin "23") (pinfunction "AMUTEC_23") (pintype "bidirectional"))
    )
    (net (code "64") (name "unconnected-(U$2-BMUTEC-Pad28)") (class "Default")
      (node (ref "U$2") (pin "28") (pinfunction "BMUTEC_28") (pintype "bidirectional"))
    )
    (net (code "65") (name "unconnected-(U$2-XTO-Pad1)") (class "Default")
      (node (ref "U$2") (pin "1") (pinfunction "XTO_1") (pintype "bidirectional"))
    )
  )
)
